# Photon_Pixel_Shield_v5.net
KiCad netlist of a schematic drawn in EAGLE
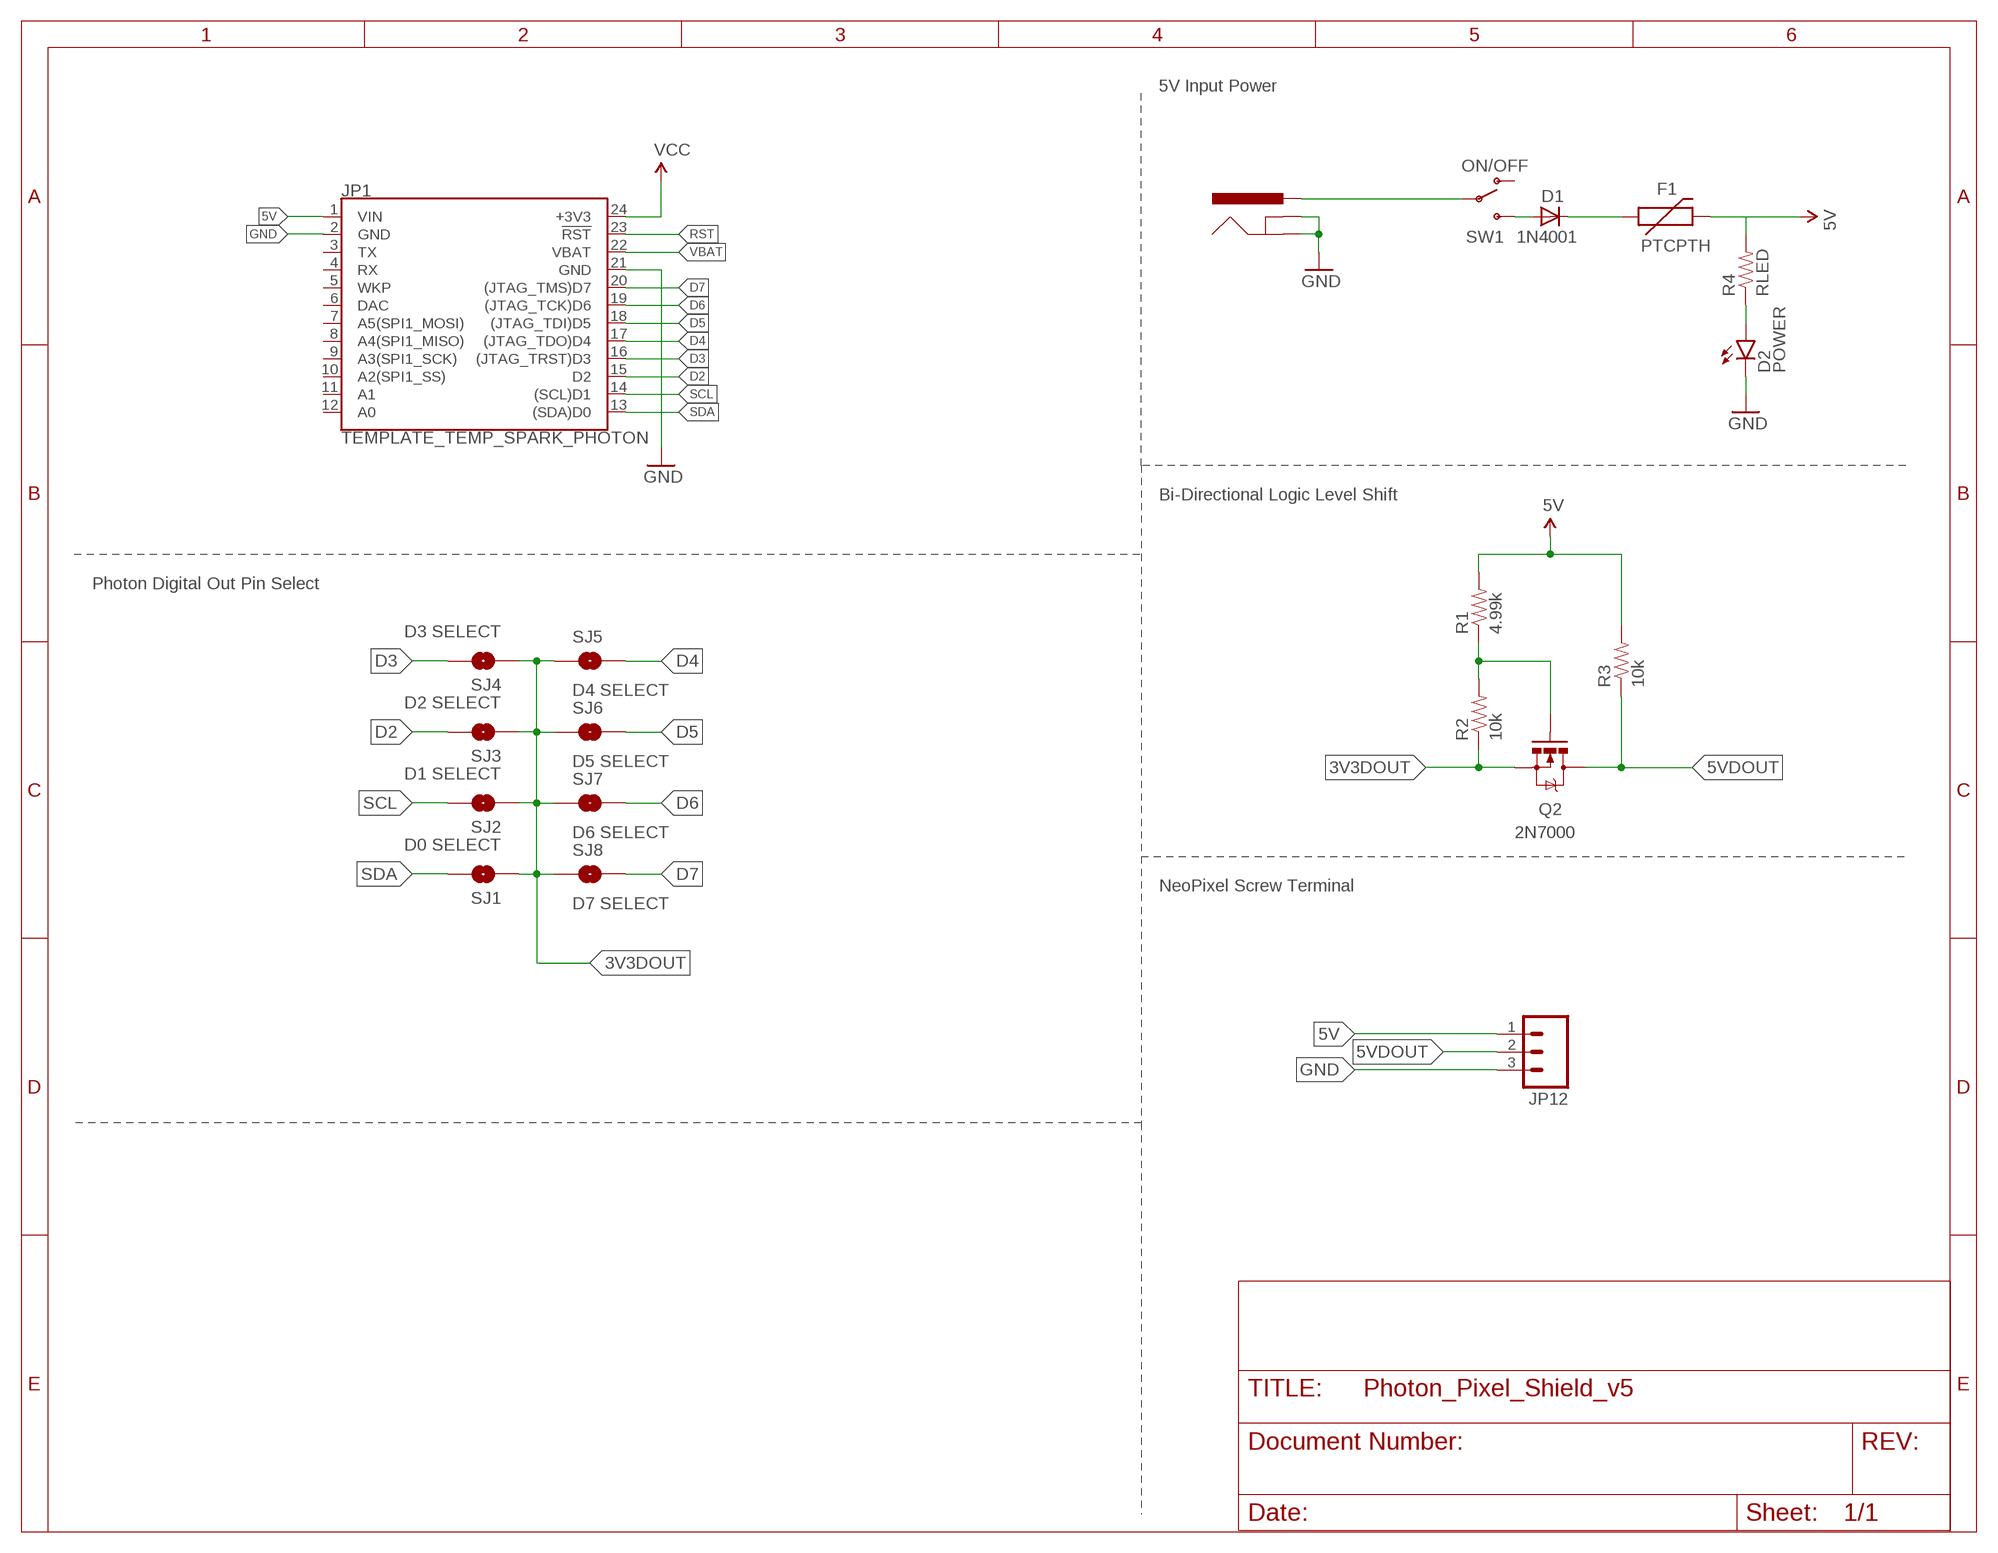
[diagram p0: schematic, sheet 1]

(export (version "E")
  (design (tool "Eeschema 10.0.6"))
  (components
    (comp (ref "D1")
      (value "1N4001")
      (footprint "eagle-import:DIODE-0.4")
      (libsource (lib "eagle-import") (part "DIODEPTH"))
    )
    (comp (ref "D2")
      (value "POWER")
      (footprint "eagle-import:LED3MM")
      (libsource (lib "eagle-import") (part "LED3MM"))
    )
    (comp (ref "F1")
      (value "PTCPTH")
      (footprint "eagle-import:PTC")
      (libsource (lib "eagle-import") (part "PTCPTH"))
    )
    (comp (ref "J1")
      (value "POWER_JACKPTH")
      (footprint "eagle-import:POWER_JACK_PTH")
      (libsource (lib "eagle-import") (part "POWER_JACKPTH"))
    )
    (comp (ref "JP1")
      (value "TEMPLATE_TEMP_SPARK_PHOTON")
      (footprint "eagle-import:TEMPLATE_TEMP_SPARK_PHOTON")
      (libsource (lib "eagle-import") (part "TEMPLATE_TEMP_SPARK_PHOTON"))
    )
    (comp (ref "JP12")
      (value "M03SCREW")
      (footprint "eagle-import:SCREWTERMINAL-3.5MM-3")
      (libsource (lib "eagle-import") (part "M03SCREW"))
    )
    (comp (ref "Q2")
      (value "2N7000")
      (footprint "eagle-import:TO-92")
      (libsource (lib "eagle-import") (part "MOSFET-NCHANNEL2N7000"))
    )
    (comp (ref "R1")
      (value "4.99k")
      (footprint "eagle-import:AXIAL-0.3")
      (libsource (lib "eagle-import") (part "10KOHM-1/4W-1%(PTH)HORIZ"))
    )
    (comp (ref "R2")
      (value "10k")
      (footprint "eagle-import:AXIAL-0.3")
      (libsource (lib "eagle-import") (part "10KOHM-1/4W-1%(PTH)HORIZ"))
    )
    (comp (ref "R3")
      (value "10k")
      (footprint "eagle-import:AXIAL-0.3")
      (libsource (lib "eagle-import") (part "10KOHM-1/4W-1%(PTH)HORIZ"))
    )
    (comp (ref "R4")
      (value "RLED")
      (footprint "eagle-import:AXIAL-0.3")
      (libsource (lib "eagle-import") (part "10KOHM-1/4W-1%(PTH)HORIZ"))
    )
    (comp (ref "SJ1")
      (value "D0 SELECT")
      (footprint "eagle-import:SJ_2S-NO")
      (libsource (lib "eagle-import") (part "SOLDERJUMPERNO"))
    )
    (comp (ref "SJ2")
      (value "D1 SELECT")
      (footprint "eagle-import:SJ_2S-NO")
      (libsource (lib "eagle-import") (part "SOLDERJUMPERNO"))
    )
    (comp (ref "SJ3")
      (value "D2 SELECT")
      (footprint "eagle-import:SJ_2S-NO")
      (libsource (lib "eagle-import") (part "SOLDERJUMPERNO"))
    )
    (comp (ref "SJ4")
      (value "D3 SELECT")
      (footprint "eagle-import:SJ_2S-NO")
      (libsource (lib "eagle-import") (part "SOLDERJUMPERNO"))
    )
    (comp (ref "SJ5")
      (value "D4 SELECT")
      (footprint "eagle-import:SJ_2S-NO")
      (libsource (lib "eagle-import") (part "SOLDERJUMPERNO"))
    )
    (comp (ref "SJ6")
      (value "D5 SELECT")
      (footprint "eagle-import:SJ_2S-NO")
      (libsource (lib "eagle-import") (part "SOLDERJUMPERNO"))
    )
    (comp (ref "SJ7")
      (value "D6 SELECT")
      (footprint "eagle-import:SJ_2S-NO")
      (libsource (lib "eagle-import") (part "SOLDERJUMPERNO"))
    )
    (comp (ref "SJ8")
      (value "D7 SELECT")
      (footprint "eagle-import:SJ_2S-NO")
      (libsource (lib "eagle-import") (part "SOLDERJUMPERNO"))
    )
    (comp (ref "SW1")
      (value "ON/OFF")
      (footprint "eagle-import:SWITCH-SPST")
      (libsource (lib "eagle-import") (part "SWITCH-SPSTPTH"))
    )
  )
  (nets
    (net (code "1") (name "3V3DOUT") (class "Default")
      (node (ref "Q2") (pin "1") (pinfunction "S_1") (pintype "passive"))
      (node (ref "R2") (pin "P$1") (pinfunction "1_P$1") (pintype "passive"))
      (node (ref "SJ1") (pin "1") (pinfunction "1_1") (pintype "passive"))
      (node (ref "SJ2") (pin "1") (pinfunction "1_1") (pintype "passive"))
      (node (ref "SJ3") (pin "1") (pinfunction "1_1") (pintype "passive"))
      (node (ref "SJ4") (pin "1") (pinfunction "1_1") (pintype "passive"))
      (node (ref "SJ5") (pin "1") (pinfunction "1_1") (pintype "passive"))
      (node (ref "SJ6") (pin "1") (pinfunction "1_1") (pintype "passive"))
      (node (ref "SJ7") (pin "1") (pinfunction "1_1") (pintype "passive"))
      (node (ref "SJ8") (pin "1") (pinfunction "1_1") (pintype "passive"))
    )
    (net (code "2") (name "5V") (class "Default")
      (node (ref "F1") (pin "P$2") (pinfunction "2_P$2") (pintype "bidirectional"))
      (node (ref "JP1") (pin "1") (pinfunction "VIN_1") (pintype "bidirectional"))
      (node (ref "JP12") (pin "1") (pinfunction "1_1") (pintype "passive"))
      (node (ref "R1") (pin "P$2") (pinfunction "2_P$2") (pintype "passive"))
      (node (ref "R3") (pin "P$2") (pinfunction "2_P$2") (pintype "passive"))
      (node (ref "R4") (pin "P$2") (pinfunction "2_P$2") (pintype "passive"))
    )
    (net (code "3") (name "5VDOUT") (class "Default")
      (node (ref "JP12") (pin "2") (pinfunction "2_2") (pintype "passive"))
      (node (ref "Q2") (pin "3") (pinfunction "D_3") (pintype "passive"))
      (node (ref "R3") (pin "P$1") (pinfunction "1_P$1") (pintype "passive"))
    )
    (net (code "4") (name "D2") (class "Default")
      (node (ref "JP1") (pin "15") (pinfunction "D2_15") (pintype "bidirectional"))
      (node (ref "SJ3") (pin "2") (pinfunction "2_2") (pintype "passive"))
    )
    (net (code "5") (name "D3") (class "Default")
      (node (ref "JP1") (pin "16") (pinfunction "(JTAG_TRST)D3_16") (pintype "bidirectional"))
      (node (ref "SJ4") (pin "2") (pinfunction "2_2") (pintype "passive"))
    )
    (net (code "6") (name "D4") (class "Default")
      (node (ref "JP1") (pin "17") (pinfunction "(JTAG_TDO)D4_17") (pintype "bidirectional"))
      (node (ref "SJ5") (pin "2") (pinfunction "2_2") (pintype "passive"))
    )
    (net (code "7") (name "D5") (class "Default")
      (node (ref "JP1") (pin "18") (pinfunction "(JTAG_TDI)D5_18") (pintype "bidirectional"))
      (node (ref "SJ6") (pin "2") (pinfunction "2_2") (pintype "passive"))
    )
    (net (code "8") (name "D6") (class "Default")
      (node (ref "JP1") (pin "19") (pinfunction "(JTAG_TCK)D6_19") (pintype "bidirectional"))
      (node (ref "SJ7") (pin "2") (pinfunction "2_2") (pintype "passive"))
    )
    (net (code "9") (name "D7") (class "Default")
      (node (ref "JP1") (pin "20") (pinfunction "(JTAG_TMS)D7_20") (pintype "bidirectional"))
      (node (ref "SJ8") (pin "2") (pinfunction "2_2") (pintype "passive"))
    )
    (net (code "10") (name "GND") (class "Default")
      (node (ref "D2") (pin "K") (pinfunction "C_K") (pintype "passive"))
      (node (ref "J1") (pin "GND") (pinfunction "GND_GND") (pintype "bidirectional"))
      (node (ref "J1") (pin "GNDBREAK") (pinfunction "GNDBREAK_GNDBREAK") (pintype "bidirectional"))
      (node (ref "JP1") (pin "2") (pinfunction "GND_2") (pintype "bidirectional"))
      (node (ref "JP1") (pin "21") (pinfunction "GND_21") (pintype "bidirectional"))
      (node (ref "JP12") (pin "3") (pinfunction "3_3") (pintype "passive"))
    )
    (net (code "11") (name "Net-(F1-1)") (class "Default")
      (node (ref "D1") (pin "C") (pinfunction "C_C") (pintype "passive"))
      (node (ref "F1") (pin "P$1") (pinfunction "1_P$1") (pintype "bidirectional"))
    )
    (net (code "12") (name "Net-(Q2-G)") (class "Default")
      (node (ref "Q2") (pin "2") (pinfunction "G_2") (pintype "passive"))
      (node (ref "R1") (pin "P$1") (pinfunction "1_P$1") (pintype "passive"))
      (node (ref "R2") (pin "P$2") (pinfunction "2_P$2") (pintype "passive"))
    )
    (net (code "13") (name "Net-(R4-1)") (class "Default")
      (node (ref "D2") (pin "A") (pinfunction "A_A") (pintype "passive"))
      (node (ref "R4") (pin "P$1") (pinfunction "1_P$1") (pintype "passive"))
    )
    (net (code "14") (name "Net-(SW1-P)") (class "Default")
      (node (ref "J1") (pin "PWR") (pinfunction "PWR_PWR") (pintype "bidirectional"))
      (node (ref "SW1") (pin "2") (pinfunction "P_2") (pintype "passive"))
    )
    (net (code "15") (name "Net-(SW1-S)") (class "Default")
      (node (ref "D1") (pin "A") (pinfunction "A_A") (pintype "passive"))
      (node (ref "SW1") (pin "3") (pinfunction "S_3") (pintype "passive"))
    )
    (net (code "16") (name "RST") (class "Default")
      (node (ref "JP1") (pin "23") (pinfunction "~{RST}_23") (pintype "bidirectional"))
    )
    (net (code "17") (name "SCL") (class "Default")
      (node (ref "JP1") (pin "14") (pinfunction "(SCL)D1_14") (pintype "bidirectional"))
      (node (ref "SJ2") (pin "2") (pinfunction "2_2") (pintype "passive"))
    )
    (net (code "18") (name "SDA") (class "Default")
      (node (ref "JP1") (pin "13") (pinfunction "(SDA)D0_13") (pintype "bidirectional"))
      (node (ref "SJ1") (pin "2") (pinfunction "2_2") (pintype "passive"))
    )
    (net (code "19") (name "VBAT") (class "Default")
      (node (ref "JP1") (pin "22") (pinfunction "VBAT_22") (pintype "bidirectional"))
    )
    (net (code "20") (name "VCC") (class "Default")
      (node (ref "JP1") (pin "24") (pinfunction "+3V3_24") (pintype "bidirectional"))
    )
    (net (code "21") (name "unconnected-(JP1-A0-Pad12)") (class "Default")
      (node (ref "JP1") (pin "12") (pinfunction "A0_12") (pintype "bidirectional"))
    )
    (net (code "22") (name "unconnected-(JP1-A1-Pad11)") (class "Default")
      (node (ref "JP1") (pin "11") (pinfunction "A1_11") (pintype "bidirectional"))
    )
    (net (code "23") (name "unconnected-(JP1-A2(SPI1_SS)-Pad10)") (class "Default")
      (node (ref "JP1") (pin "10") (pinfunction "A2(SPI1_SS)_10") (pintype "bidirectional"))
    )
    (net (code "24") (name "unconnected-(JP1-A3(SPI1_SCK)-Pad9)") (class "Default")
      (node (ref "JP1") (pin "9") (pinfunction "A3(SPI1_SCK)_9") (pintype "bidirectional"))
    )
    (net (code "25") (name "unconnected-(JP1-A4(SPI1_MISO)-Pad8)") (class "Default")
      (node (ref "JP1") (pin "8") (pinfunction "A4(SPI1_MISO)_8") (pintype "bidirectional"))
    )
    (net (code "26") (name "unconnected-(JP1-A5(SPI1_MOSI)-Pad7)") (class "Default")
      (node (ref "JP1") (pin "7") (pinfunction "A5(SPI1_MOSI)_7") (pintype "bidirectional"))
    )
    (net (code "27") (name "unconnected-(JP1-DAC-Pad6)") (class "Default")
      (node (ref "JP1") (pin "6") (pinfunction "DAC_6") (pintype "bidirectional"))
    )
    (net (code "28") (name "unconnected-(JP1-RX-Pad4)") (class "Default")
      (node (ref "JP1") (pin "4") (pinfunction "RX_4") (pintype "bidirectional"))
    )
    (net (code "29") (name "unconnected-(JP1-TX-Pad3)") (class "Default")
      (node (ref "JP1") (pin "3") (pinfunction "TX_3") (pintype "bidirectional"))
    )
    (net (code "30") (name "unconnected-(JP1-WKP-Pad5)") (class "Default")
      (node (ref "JP1") (pin "5") (pinfunction "WKP_5") (pintype "bidirectional"))
    )
    (net (code "31") (name "unconnected-(SW1-O-Pad1)") (class "Default")
      (node (ref "SW1") (pin "1") (pinfunction "O_1") (pintype "passive"))
    )
  )
)
